# Sheet1.net
KiCad netlist of a schematic drawn in Altium Designer
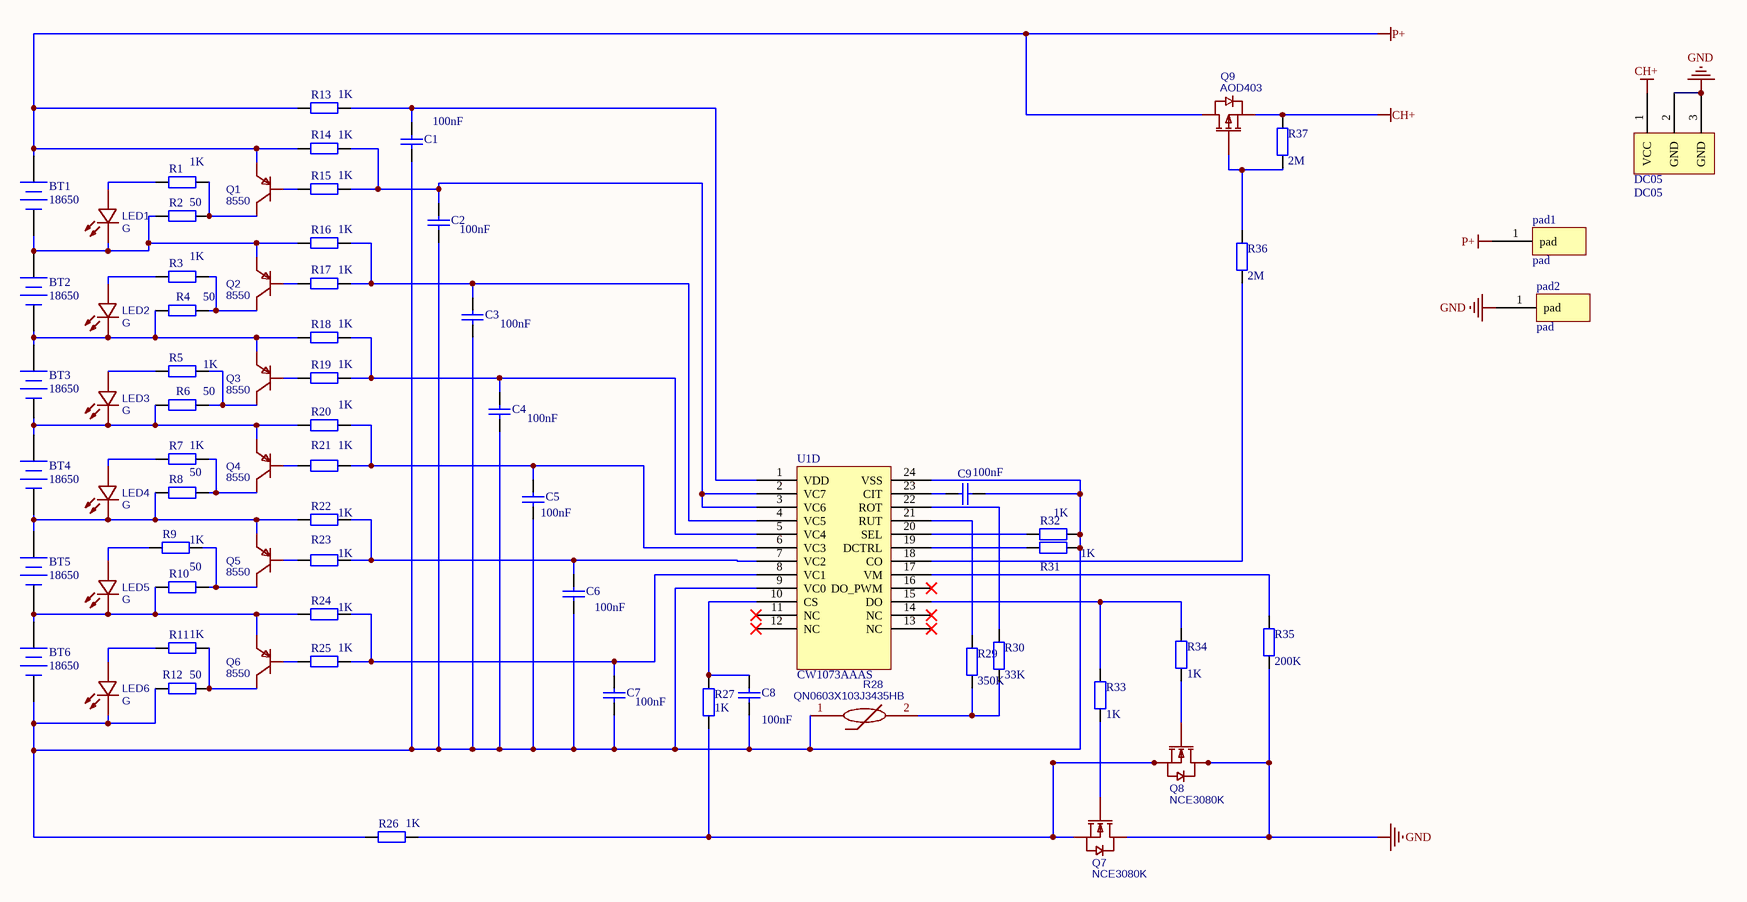
[diagram p0: Sheet1.SchDoc]

(export (version "E")
  (design (tool "Eeschema 10.0.6"))
  (components
    (comp (ref "BT1")
      (value "18650")
      (footprint "18650-贴片")
      (description "Multicell Battery")
      (fields (field (name "PUBLISHER") "Altium Limited"))
      (libsource (lib "Miscellaneous Devices") (part "Battery"))
    )
    (comp (ref "BT2")
      (value "18650")
      (footprint "18650-贴片")
      (description "Multicell Battery")
      (fields (field (name "PUBLISHER") "Altium Limited"))
      (libsource (lib "Miscellaneous Devices") (part "Battery"))
    )
    (comp (ref "BT3")
      (value "18650")
      (footprint "18650-贴片")
      (description "Multicell Battery")
      (fields (field (name "PUBLISHER") "Altium Limited"))
      (libsource (lib "Miscellaneous Devices") (part "Battery"))
    )
    (comp (ref "BT4")
      (value "18650")
      (footprint "18650-贴片")
      (description "Multicell Battery")
      (fields (field (name "PUBLISHER") "Altium Limited"))
      (libsource (lib "Miscellaneous Devices") (part "Battery"))
    )
    (comp (ref "BT5")
      (value "18650")
      (footprint "18650-贴片")
      (description "Multicell Battery")
      (fields (field (name "PUBLISHER") "Altium Limited"))
      (libsource (lib "Miscellaneous Devices") (part "Battery"))
    )
    (comp (ref "BT6")
      (value "18650")
      (footprint "18650-贴片")
      (description "Multicell Battery")
      (fields (field (name "PUBLISHER") "Altium Limited"))
      (libsource (lib "Miscellaneous Devices") (part "Battery"))
    )
    (comp (ref "C1")
      (value "100nF")
      (footprint "0805_C")
      (description "Capacitor")
      (fields (field (name "PUBLISHER") "Altium Limited"))
      (libsource (lib "Miscellaneous Devices") (part "Cap"))
    )
    (comp (ref "C2")
      (value "100nF")
      (footprint "0805_C")
      (description "Capacitor")
      (fields (field (name "PUBLISHER") "Altium Limited"))
      (libsource (lib "Miscellaneous Devices") (part "Cap"))
    )
    (comp (ref "C3")
      (value "100nF")
      (footprint "0805_C")
      (description "Capacitor")
      (fields (field (name "PUBLISHER") "Altium Limited"))
      (libsource (lib "Miscellaneous Devices") (part "Cap"))
    )
    (comp (ref "C4")
      (value "100nF")
      (footprint "0805_C")
      (description "Capacitor")
      (fields (field (name "PUBLISHER") "Altium Limited"))
      (libsource (lib "Miscellaneous Devices") (part "Cap"))
    )
    (comp (ref "C5")
      (value "100nF")
      (footprint "0805_C")
      (description "Capacitor")
      (fields (field (name "PUBLISHER") "Altium Limited"))
      (libsource (lib "Miscellaneous Devices") (part "Cap"))
    )
    (comp (ref "C6")
      (value "100nF")
      (footprint "0805_C")
      (description "Capacitor")
      (fields (field (name "PUBLISHER") "Altium Limited"))
      (libsource (lib "Miscellaneous Devices") (part "Cap"))
    )
    (comp (ref "C7")
      (value "100nF")
      (footprint "0805_C")
      (description "Capacitor")
      (fields (field (name "PUBLISHER") "Altium Limited"))
      (libsource (lib "Miscellaneous Devices") (part "Cap"))
    )
    (comp (ref "C8")
      (value "100nF")
      (footprint "0805_C")
      (description "Capacitor")
      (fields (field (name "PUBLISHER") "Altium Limited"))
      (libsource (lib "Miscellaneous Devices") (part "Cap"))
    )
    (comp (ref "C9")
      (value "100nF")
      (footprint "0805_C")
      (description "Capacitor")
      (fields (field (name "PUBLISHER") "Altium Limited"))
      (libsource (lib "Miscellaneous Devices") (part "Cap"))
    )
    (comp (ref "DC05")
      (value "DC05")
      (footprint "DC-005 - duplicate")
      (description "DC05电源")
      (libsource (lib "elin私人订制") (part "DC05"))
    )
    (comp (ref "LED1")
      (value "G")
      (footprint "LED_0805")
      (fields
        (field (name "BOM_SUPPLIER PART") "C264445")
        (field (name "BOM_MANUFACTURER PART") "19-21CUTD/S3484/TR8")
        (field (name "CONTRIBUTOR") "LCSC")
      )
      (libsource (lib "altium-import") (part "root_1_G_"))
    )
    (comp (ref "LED2")
      (value "G")
      (footprint "LED_0805")
      (fields
        (field (name "BOM_SUPPLIER PART") "C264445")
        (field (name "BOM_MANUFACTURER PART") "19-21CUTD/S3484/TR8")
        (field (name "CONTRIBUTOR") "LCSC")
      )
      (libsource (lib "altium-import") (part "root_1_G_"))
    )
    (comp (ref "LED3")
      (value "G")
      (footprint "LED_0805")
      (fields
        (field (name "BOM_SUPPLIER PART") "C264445")
        (field (name "BOM_MANUFACTURER PART") "19-21CUTD/S3484/TR8")
        (field (name "CONTRIBUTOR") "LCSC")
      )
      (libsource (lib "altium-import") (part "root_1_G_"))
    )
    (comp (ref "LED4")
      (value "G")
      (footprint "LED_0805")
      (fields
        (field (name "BOM_SUPPLIER PART") "C264445")
        (field (name "BOM_MANUFACTURER PART") "19-21CUTD/S3484/TR8")
        (field (name "CONTRIBUTOR") "LCSC")
      )
      (libsource (lib "altium-import") (part "root_1_G_"))
    )
    (comp (ref "LED5")
      (value "G")
      (footprint "LED_0805")
      (fields
        (field (name "BOM_SUPPLIER PART") "C264445")
        (field (name "BOM_MANUFACTURER PART") "19-21CUTD/S3484/TR8")
        (field (name "CONTRIBUTOR") "LCSC")
      )
      (libsource (lib "altium-import") (part "root_1_G_"))
    )
    (comp (ref "LED6")
      (value "G")
      (footprint "LED_0805")
      (fields
        (field (name "BOM_SUPPLIER PART") "C264445")
        (field (name "BOM_MANUFACTURER PART") "19-21CUTD/S3484/TR8")
        (field (name "CONTRIBUTOR") "LCSC")
      )
      (libsource (lib "altium-import") (part "root_1_G_"))
    )
    (comp (ref "pad1") (value "pad") (footprint "PAD3*3") (libsource (lib "elin私人订制") (part "pad1")))
    (comp (ref "pad2") (value "pad") (footprint "PAD3*3") (libsource (lib "elin私人订制") (part "pad1")))
    (comp (ref "Q1")
      (value "8550")
      (footprint "SOT23")
      (fields
        (field (name "BOM_SUPPLIER PART") "C305484")
        (field (name "BOM_MANUFACTURER PART") "S8550M-D")
        (field (name "CONTRIBUTOR") "LCSC")
      )
      (libsource (lib "altium-import") (part "root_2_8550_"))
    )
    (comp (ref "Q2")
      (value "8550")
      (footprint "SOT23")
      (fields
        (field (name "BOM_SUPPLIER PART") "C305484")
        (field (name "BOM_MANUFACTURER PART") "S8550M-D")
        (field (name "CONTRIBUTOR") "LCSC")
      )
      (libsource (lib "altium-import") (part "root_2_8550_"))
    )
    (comp (ref "Q3")
      (value "8550")
      (footprint "SOT23")
      (fields
        (field (name "BOM_SUPPLIER PART") "C305484")
        (field (name "BOM_MANUFACTURER PART") "S8550M-D")
        (field (name "CONTRIBUTOR") "LCSC")
      )
      (libsource (lib "altium-import") (part "root_2_8550_"))
    )
    (comp (ref "Q4")
      (value "8550")
      (footprint "SOT23")
      (fields
        (field (name "BOM_SUPPLIER PART") "C305484")
        (field (name "BOM_MANUFACTURER PART") "S8550M-D")
        (field (name "CONTRIBUTOR") "LCSC")
      )
      (libsource (lib "altium-import") (part "root_2_8550_"))
    )
    (comp (ref "Q5")
      (value "8550")
      (footprint "SOT23")
      (fields
        (field (name "BOM_SUPPLIER PART") "C305484")
        (field (name "BOM_MANUFACTURER PART") "S8550M-D")
        (field (name "CONTRIBUTOR") "LCSC")
      )
      (libsource (lib "altium-import") (part "root_2_8550_"))
    )
    (comp (ref "Q6")
      (value "8550")
      (footprint "SOT23")
      (fields
        (field (name "BOM_SUPPLIER PART") "C305484")
        (field (name "BOM_MANUFACTURER PART") "S8550M-D")
        (field (name "CONTRIBUTOR") "LCSC")
      )
      (libsource (lib "altium-import") (part "root_2_8550_"))
    )
    (comp (ref "Q7")
      (value "NCE3080K")
      (footprint "LC-TO-252-2")
      (fields (field (name "BOM_SUPPLIER PART") "C108901"))
      (libsource (lib "altium-import") (part "root_3_NCE3080K_"))
    )
    (comp (ref "Q8")
      (value "NCE3080K")
      (footprint "LC-TO-252-2")
      (fields (field (name "BOM_SUPPLIER PART") "C108901"))
      (libsource (lib "altium-import") (part "root_3_NCE3080K_"))
    )
    (comp (ref "Q9")
      (value "AOD403")
      (footprint "LC-TO-252-2")
      (fields (field (name "BOM_SUPPLIER PART") "C28969"))
      (libsource (lib "altium-import") (part "root_1_AOD403_"))
    )
    (comp (ref "R1")
      (value "1K")
      (footprint "0603-R")
      (description "Resistor")
      (fields (field (name "PUBLISHER") "Altium Limited"))
      (libsource (lib "Miscellaneous Devices") (part "Res2"))
    )
    (comp (ref "R2")
      (value "50")
      (footprint "LC-2512_R")
      (description "Resistor")
      (fields (field (name "PUBLISHER") "Altium Limited"))
      (libsource (lib "Miscellaneous Devices") (part "Res2"))
    )
    (comp (ref "R3")
      (value "1K")
      (footprint "0603-R")
      (description "Resistor")
      (fields (field (name "PUBLISHER") "Altium Limited"))
      (libsource (lib "Miscellaneous Devices") (part "Res2"))
    )
    (comp (ref "R4")
      (value "50")
      (footprint "LC-2512_R")
      (description "Resistor")
      (fields (field (name "PUBLISHER") "Altium Limited"))
      (libsource (lib "Miscellaneous Devices") (part "Res2"))
    )
    (comp (ref "R5")
      (value "1K")
      (footprint "0603-R")
      (description "Resistor")
      (fields (field (name "PUBLISHER") "Altium Limited"))
      (libsource (lib "Miscellaneous Devices") (part "Res2"))
    )
    (comp (ref "R6")
      (value "50")
      (footprint "LC-2512_R")
      (description "Resistor")
      (fields (field (name "PUBLISHER") "Altium Limited"))
      (libsource (lib "Miscellaneous Devices") (part "Res2"))
    )
    (comp (ref "R7")
      (value "1K")
      (footprint "0603-R")
      (description "Resistor")
      (fields (field (name "PUBLISHER") "Altium Limited"))
      (libsource (lib "Miscellaneous Devices") (part "Res2"))
    )
    (comp (ref "R8")
      (value "50")
      (footprint "LC-2512_R")
      (description "Resistor")
      (fields (field (name "PUBLISHER") "Altium Limited"))
      (libsource (lib "Miscellaneous Devices") (part "Res2"))
    )
    (comp (ref "R9")
      (value "1K")
      (footprint "0603-R")
      (description "Resistor")
      (fields (field (name "PUBLISHER") "Altium Limited"))
      (libsource (lib "Miscellaneous Devices") (part "Res2"))
    )
    (comp (ref "R10")
      (value "50")
      (footprint "LC-2512_R")
      (description "Resistor")
      (fields (field (name "PUBLISHER") "Altium Limited"))
      (libsource (lib "Miscellaneous Devices") (part "Res2"))
    )
    (comp (ref "R11")
      (value "1K")
      (footprint "0603-R")
      (description "Resistor")
      (fields (field (name "PUBLISHER") "Altium Limited"))
      (libsource (lib "Miscellaneous Devices") (part "Res2"))
    )
    (comp (ref "R12")
      (value "50")
      (footprint "LC-2512_R")
      (description "Resistor")
      (fields (field (name "PUBLISHER") "Altium Limited"))
      (libsource (lib "Miscellaneous Devices") (part "Res2"))
    )
    (comp (ref "R13")
      (value "1K")
      (footprint "0603-R")
      (description "Resistor")
      (fields (field (name "PUBLISHER") "Altium Limited"))
      (libsource (lib "Miscellaneous Devices") (part "Res2"))
    )
    (comp (ref "R14")
      (value "1K")
      (footprint "0603-R")
      (description "Resistor")
      (fields (field (name "PUBLISHER") "Altium Limited"))
      (libsource (lib "Miscellaneous Devices") (part "Res2"))
    )
    (comp (ref "R15")
      (value "1K")
      (footprint "0603-R")
      (description "Resistor")
      (fields (field (name "PUBLISHER") "Altium Limited"))
      (libsource (lib "Miscellaneous Devices") (part "Res2"))
    )
    (comp (ref "R16")
      (value "1K")
      (footprint "0603-R")
      (description "Resistor")
      (fields (field (name "PUBLISHER") "Altium Limited"))
      (libsource (lib "Miscellaneous Devices") (part "Res2"))
    )
    (comp (ref "R17")
      (value "1K")
      (footprint "0603-R")
      (description "Resistor")
      (fields (field (name "PUBLISHER") "Altium Limited"))
      (libsource (lib "Miscellaneous Devices") (part "Res2"))
    )
    (comp (ref "R18")
      (value "1K")
      (footprint "0603-R")
      (description "Resistor")
      (fields (field (name "PUBLISHER") "Altium Limited"))
      (libsource (lib "Miscellaneous Devices") (part "Res2"))
    )
    (comp (ref "R19")
      (value "1K")
      (footprint "0603-R")
      (description "Resistor")
      (fields (field (name "PUBLISHER") "Altium Limited"))
      (libsource (lib "Miscellaneous Devices") (part "Res2"))
    )
    (comp (ref "R20")
      (value "1K")
      (footprint "0603-R")
      (description "Resistor")
      (fields (field (name "PUBLISHER") "Altium Limited"))
      (libsource (lib "Miscellaneous Devices") (part "Res2"))
    )
    (comp (ref "R21")
      (value "1K")
      (footprint "0603-R")
      (description "Resistor")
      (fields (field (name "PUBLISHER") "Altium Limited"))
      (libsource (lib "Miscellaneous Devices") (part "Res2"))
    )
    (comp (ref "R22")
      (value "1K")
      (footprint "0603-R")
      (description "Resistor")
      (fields (field (name "PUBLISHER") "Altium Limited"))
      (libsource (lib "Miscellaneous Devices") (part "Res2"))
    )
    (comp (ref "R23")
      (value "1K")
      (footprint "0603-R")
      (description "Resistor")
      (fields (field (name "PUBLISHER") "Altium Limited"))
      (libsource (lib "Miscellaneous Devices") (part "Res2"))
    )
    (comp (ref "R24")
      (value "1K")
      (footprint "0603-R")
      (description "Resistor")
      (fields (field (name "PUBLISHER") "Altium Limited"))
      (libsource (lib "Miscellaneous Devices") (part "Res2"))
    )
    (comp (ref "R25")
      (value "1K")
      (footprint "0603-R")
      (description "Resistor")
      (fields (field (name "PUBLISHER") "Altium Limited"))
      (libsource (lib "Miscellaneous Devices") (part "Res2"))
    )
    (comp (ref "R26")
      (value "1K")
      (footprint "0603-R")
      (description "Resistor")
      (fields (field (name "PUBLISHER") "Altium Limited"))
      (libsource (lib "Miscellaneous Devices") (part "Res2"))
    )
    (comp (ref "R27")
      (value "1K")
      (footprint "0603-R")
      (description "Resistor")
      (fields (field (name "PUBLISHER") "Altium Limited"))
      (libsource (lib "") (part "Res2_1"))
    )
    (comp (ref "R28")
      (value "QN0603X103J3435HB")
      (footprint "0603-R")
      (fields (field (name "BOM_SUPPLIER PART") "C700828") (field (name "CONTRIBUTOR") "LCSC"))
      (libsource (lib "altium-import") (part "root_0_QN0603X103J3435HB_"))
    )
    (comp (ref "R29")
      (value "350K")
      (footprint "0603-R")
      (description "Resistor")
      (fields (field (name "PUBLISHER") "Altium Limited"))
      (libsource (lib "") (part "Res2_1"))
    )
    (comp (ref "R30")
      (value "33K")
      (footprint "0603-R")
      (description "Resistor")
      (fields (field (name "PUBLISHER") "Altium Limited"))
      (libsource (lib "") (part "Res2_1"))
    )
    (comp (ref "R31")
      (value "1K")
      (footprint "0603-R")
      (description "Resistor")
      (fields (field (name "PUBLISHER") "Altium Limited"))
      (libsource (lib "Miscellaneous Devices") (part "Res2"))
    )
    (comp (ref "R32")
      (value "1K")
      (footprint "0603-R")
      (description "Resistor")
      (fields (field (name "PUBLISHER") "Altium Limited"))
      (libsource (lib "Miscellaneous Devices") (part "Res2"))
    )
    (comp (ref "R33")
      (value "1K")
      (footprint "0603-R")
      (description "Resistor")
      (fields (field (name "PUBLISHER") "Altium Limited"))
      (libsource (lib "") (part "Res2_1"))
    )
    (comp (ref "R34")
      (value "1K")
      (footprint "0603-R")
      (description "Resistor")
      (fields (field (name "PUBLISHER") "Altium Limited"))
      (libsource (lib "") (part "Res2_1"))
    )
    (comp (ref "R35")
      (value "200K")
      (footprint "0603-R")
      (description "Resistor")
      (fields (field (name "PUBLISHER") "Altium Limited"))
      (libsource (lib "") (part "Res2_1"))
    )
    (comp (ref "R36")
      (value "2M")
      (footprint "0603-R")
      (description "Resistor")
      (fields (field (name "PUBLISHER") "Altium Limited"))
      (libsource (lib "") (part "Res2_1"))
    )
    (comp (ref "R37")
      (value "2M")
      (footprint "0603-R")
      (description "Resistor")
      (fields (field (name "PUBLISHER") "Altium Limited"))
      (libsource (lib "") (part "Res2_1"))
    )
    (comp (ref "U1")
      (value "CW1073AAAS")
      (footprint "LC-SSOP-24_208mil")
      (libsource (lib "Schlib1") (part "Component_1"))
    )
  )
  (nets
    (net (code "1") (name "CH+") (class "Default")
      (node (ref "DC05") (pin "1") (pinfunction "VCC_1") (pintype "passive"))
      (node (ref "Q9") (pin "3") (pinfunction "S_3") (pintype "passive"))
      (node (ref "R37") (pin "2") (pinfunction "2_2") (pintype "passive"))
    )
    (net (code "2") (name "GND") (class "Default")
      (node (ref "DC05") (pin "2") (pinfunction "GND_2") (pintype "passive"))
      (node (ref "DC05") (pin "3") (pinfunction "GND_3") (pintype "passive"))
      (node (ref "Q7") (pin "2") (pinfunction "D_2") (pintype "passive"))
      (node (ref "Q8") (pin "2") (pinfunction "D_2") (pintype "passive"))
      (node (ref "R35") (pin "1") (pinfunction "1_1") (pintype "passive"))
      (node (ref "pad2") (pin "1") (pinfunction "pad_1") (pintype "passive"))
    )
    (net (code "3") (name "Net-(BT1--)") (class "Default")
      (node (ref "BT1") (pin "2") (pinfunction "-_2") (pintype "passive"))
      (node (ref "BT2") (pin "1") (pinfunction "+_1") (pintype "passive"))
      (node (ref "LED1") (pin "2") (pinfunction "K_2") (pintype "passive"))
      (node (ref "Q2") (pin "2") (pinfunction "E_2") (pintype "passive"))
      (node (ref "R16") (pin "1") (pinfunction "1_1") (pintype "passive"))
      (node (ref "R2") (pin "1") (pinfunction "1_1") (pintype "passive"))
    )
    (net (code "4") (name "Net-(BT2--)") (class "Default")
      (node (ref "BT2") (pin "2") (pinfunction "-_2") (pintype "passive"))
      (node (ref "BT3") (pin "1") (pinfunction "+_1") (pintype "passive"))
      (node (ref "LED2") (pin "2") (pinfunction "K_2") (pintype "passive"))
      (node (ref "Q3") (pin "2") (pinfunction "E_2") (pintype "passive"))
      (node (ref "R18") (pin "1") (pinfunction "1_1") (pintype "passive"))
      (node (ref "R4") (pin "1") (pinfunction "1_1") (pintype "passive"))
    )
    (net (code "5") (name "Net-(BT3--)") (class "Default")
      (node (ref "BT3") (pin "2") (pinfunction "-_2") (pintype "passive"))
      (node (ref "BT4") (pin "1") (pinfunction "+_1") (pintype "passive"))
      (node (ref "LED3") (pin "2") (pinfunction "K_2") (pintype "passive"))
      (node (ref "Q4") (pin "2") (pinfunction "E_2") (pintype "passive"))
      (node (ref "R20") (pin "1") (pinfunction "1_1") (pintype "passive"))
      (node (ref "R6") (pin "1") (pinfunction "1_1") (pintype "passive"))
    )
    (net (code "6") (name "Net-(BT4--)") (class "Default")
      (node (ref "BT4") (pin "2") (pinfunction "-_2") (pintype "passive"))
      (node (ref "BT5") (pin "1") (pinfunction "+_1") (pintype "passive"))
      (node (ref "LED4") (pin "2") (pinfunction "K_2") (pintype "passive"))
      (node (ref "Q5") (pin "2") (pinfunction "E_2") (pintype "passive"))
      (node (ref "R22") (pin "1") (pinfunction "1_1") (pintype "passive"))
      (node (ref "R8") (pin "1") (pinfunction "1_1") (pintype "passive"))
    )
    (net (code "7") (name "Net-(BT5--)") (class "Default")
      (node (ref "BT5") (pin "2") (pinfunction "-_2") (pintype "passive"))
      (node (ref "BT6") (pin "1") (pinfunction "+_1") (pintype "passive"))
      (node (ref "LED5") (pin "2") (pinfunction "K_2") (pintype "passive"))
      (node (ref "Q6") (pin "2") (pinfunction "E_2") (pintype "passive"))
      (node (ref "R10") (pin "1") (pinfunction "1_1") (pintype "passive"))
      (node (ref "R24") (pin "1") (pinfunction "1_1") (pintype "passive"))
    )
    (net (code "8") (name "Net-(BT6--)") (class "Default")
      (node (ref "BT6") (pin "2") (pinfunction "-_2") (pintype "passive"))
      (node (ref "C1") (pin "2") (pinfunction "2_2") (pintype "passive"))
      (node (ref "C2") (pin "2") (pinfunction "2_2") (pintype "passive"))
      (node (ref "C3") (pin "2") (pinfunction "2_2") (pintype "passive"))
      (node (ref "C4") (pin "2") (pinfunction "2_2") (pintype "passive"))
      (node (ref "C5") (pin "2") (pinfunction "2_2") (pintype "passive"))
      (node (ref "C6") (pin "2") (pinfunction "2_2") (pintype "passive"))
      (node (ref "C7") (pin "2") (pinfunction "2_2") (pintype "passive"))
      (node (ref "C8") (pin "2") (pinfunction "2_2") (pintype "passive"))
      (node (ref "C9") (pin "1") (pinfunction "1_1") (pintype "passive"))
      (node (ref "LED6") (pin "2") (pinfunction "K_2") (pintype "passive"))
      (node (ref "R12") (pin "1") (pinfunction "1_1") (pintype "passive"))
      (node (ref "R26") (pin "1") (pinfunction "1_1") (pintype "passive"))
      (node (ref "R28") (pin "1") (pinfunction "1_1") (pintype "passive"))
      (node (ref "R31") (pin "2") (pinfunction "2_2") (pintype "passive"))
      (node (ref "R32") (pin "2") (pinfunction "2_2") (pintype "passive"))
      (node (ref "U1") (pin "24") (pinfunction "VSS_24") (pintype "passive"))
      (node (ref "U1") (pin "9") (pinfunction "VC0_9") (pintype "passive"))
    )
    (net (code "9") (name "Net-(LED1-A)") (class "Default")
      (node (ref "LED1") (pin "1") (pinfunction "A_1") (pintype "passive"))
      (node (ref "R1") (pin "1") (pinfunction "1_1") (pintype "passive"))
    )
    (net (code "10") (name "Net-(LED2-A)") (class "Default")
      (node (ref "LED2") (pin "1") (pinfunction "A_1") (pintype "passive"))
      (node (ref "R3") (pin "1") (pinfunction "1_1") (pintype "passive"))
    )
    (net (code "11") (name "Net-(LED3-A)") (class "Default")
      (node (ref "LED3") (pin "1") (pinfunction "A_1") (pintype "passive"))
      (node (ref "R5") (pin "1") (pinfunction "1_1") (pintype "passive"))
    )
    (net (code "12") (name "Net-(LED4-A)") (class "Default")
      (node (ref "LED4") (pin "1") (pinfunction "A_1") (pintype "passive"))
      (node (ref "R7") (pin "1") (pinfunction "1_1") (pintype "passive"))
    )
    (net (code "13") (name "Net-(LED5-A)") (class "Default")
      (node (ref "LED5") (pin "1") (pinfunction "A_1") (pintype "passive"))
      (node (ref "R9") (pin "1") (pinfunction "1_1") (pintype "passive"))
    )
    (net (code "14") (name "Net-(LED6-A)") (class "Default")
      (node (ref "LED6") (pin "1") (pinfunction "A_1") (pintype "passive"))
      (node (ref "R11") (pin "1") (pinfunction "1_1") (pintype "passive"))
    )
    (net (code "15") (name "Net-(Q1-B)") (class "Default")
      (node (ref "Q1") (pin "1") (pinfunction "B_1") (pintype "passive"))
      (node (ref "R15") (pin "1") (pinfunction "1_1") (pintype "passive"))
    )
    (net (code "16") (name "Net-(Q1-C)") (class "Default")
      (node (ref "Q1") (pin "3") (pinfunction "C_3") (pintype "passive"))
      (node (ref "R1") (pin "2") (pinfunction "2_2") (pintype "passive"))
      (node (ref "R2") (pin "2") (pinfunction "2_2") (pintype "passive"))
    )
    (net (code "17") (name "Net-(Q2-B)") (class "Default")
      (node (ref "Q2") (pin "1") (pinfunction "B_1") (pintype "passive"))
      (node (ref "R17") (pin "1") (pinfunction "1_1") (pintype "passive"))
    )
    (net (code "18") (name "Net-(Q2-C)") (class "Default")
      (node (ref "Q2") (pin "3") (pinfunction "C_3") (pintype "passive"))
      (node (ref "R3") (pin "2") (pinfunction "2_2") (pintype "passive"))
      (node (ref "R4") (pin "2") (pinfunction "2_2") (pintype "passive"))
    )
    (net (code "19") (name "Net-(Q3-B)") (class "Default")
      (node (ref "Q3") (pin "1") (pinfunction "B_1") (pintype "passive"))
      (node (ref "R19") (pin "1") (pinfunction "1_1") (pintype "passive"))
    )
    (net (code "20") (name "Net-(Q3-C)") (class "Default")
      (node (ref "Q3") (pin "3") (pinfunction "C_3") (pintype "passive"))
      (node (ref "R5") (pin "2") (pinfunction "2_2") (pintype "passive"))
      (node (ref "R6") (pin "2") (pinfunction "2_2") (pintype "passive"))
    )
    (net (code "21") (name "Net-(Q4-B)") (class "Default")
      (node (ref "Q4") (pin "1") (pinfunction "B_1") (pintype "passive"))
      (node (ref "R21") (pin "1") (pinfunction "1_1") (pintype "passive"))
    )
    (net (code "22") (name "Net-(Q4-C)") (class "Default")
      (node (ref "Q4") (pin "3") (pinfunction "C_3") (pintype "passive"))
      (node (ref "R7") (pin "2") (pinfunction "2_2") (pintype "passive"))
      (node (ref "R8") (pin "2") (pinfunction "2_2") (pintype "passive"))
    )
    (net (code "23") (name "Net-(Q5-B)") (class "Default")
      (node (ref "Q5") (pin "1") (pinfunction "B_1") (pintype "passive"))
      (node (ref "R23") (pin "1") (pinfunction "1_1") (pintype "passive"))
    )
    (net (code "24") (name "Net-(Q5-C)") (class "Default")
      (node (ref "Q5") (pin "3") (pinfunction "C_3") (pintype "passive"))
      (node (ref "R10") (pin "2") (pinfunction "2_2") (pintype "passive"))
      (node (ref "R9") (pin "2") (pinfunction "2_2") (pintype "passive"))
    )
    (net (code "25") (name "Net-(Q6-B)") (class "Default")
      (node (ref "Q6") (pin "1") (pinfunction "B_1") (pintype "passive"))
      (node (ref "R25") (pin "1") (pinfunction "1_1") (pintype "passive"))
    )
    (net (code "26") (name "Net-(Q6-C)") (class "Default")
      (node (ref "Q6") (pin "3") (pinfunction "C_3") (pintype "passive"))
      (node (ref "R11") (pin "2") (pinfunction "2_2") (pintype "passive"))
      (node (ref "R12") (pin "2") (pinfunction "2_2") (pintype "passive"))
    )
    (net (code "27") (name "Net-(Q7-G)") (class "Default")
      (node (ref "Q7") (pin "1") (pinfunction "G_1") (pintype "passive"))
      (node (ref "R33") (pin "1") (pinfunction "1_1") (pintype "passive"))
    )
    (net (code "28") (name "Net-(Q7-S)") (class "Default")
      (node (ref "Q7") (pin "3") (pinfunction "S_3") (pintype "passive"))
      (node (ref "Q8") (pin "3") (pinfunction "S_3") (pintype "passive"))
      (node (ref "R26") (pin "2") (pinfunction "2_2") (pintype "passive"))
      (node (ref "R27") (pin "1") (pinfunction "1_1") (pintype "passive"))
    )
    (net (code "29") (name "Net-(Q8-G)") (class "Default")
      (node (ref "Q8") (pin "1") (pinfunction "G_1") (pintype "passive"))
      (node (ref "R34") (pin "1") (pinfunction "1_1") (pintype "passive"))
    )
    (net (code "30") (name "Net-(Q9-G)") (class "Default")
      (node (ref "Q9") (pin "1") (pinfunction "G_1") (pintype "passive"))
      (node (ref "R36") (pin "2") (pinfunction "2_2") (pintype "passive"))
      (node (ref "R37") (pin "1") (pinfunction "1_1") (pintype "passive"))
    )
    (net (code "31") (name "Net-(R28-Pad2)") (class "Default")
      (node (ref "R28") (pin "2") (pinfunction "2_2") (pintype "passive"))
      (node (ref "R29") (pin "1") (pinfunction "1_1") (pintype "passive"))
      (node (ref "R30") (pin "1") (pinfunction "1_1") (pintype "passive"))
    )
    (net (code "32") (name "Net-(U1D-CIT)") (class "Default")
      (node (ref "C9") (pin "2") (pinfunction "2_2") (pintype "passive"))
      (node (ref "U1") (pin "23") (pinfunction "CIT_23") (pintype "passive"))
    )
    (net (code "33") (name "Net-(U1D-CO)") (class "Default")
      (node (ref "R36") (pin "1") (pinfunction "1_1") (pintype "passive"))
      (node (ref "U1") (pin "18") (pinfunction "CO_18") (pintype "passive"))
    )
    (net (code "34") (name "Net-(U1D-CS)") (class "Default")
      (node (ref "C8") (pin "1") (pinfunction "1_1") (pintype "passive"))
      (node (ref "R27") (pin "2") (pinfunction "2_2") (pintype "passive"))
      (node (ref "U1") (pin "10") (pinfunction "CS_10") (pintype "passive"))
    )
    (net (code "35") (name "Net-(U1D-DCTRL)") (class "Default")
      (node (ref "R31") (pin "1") (pinfunction "1_1") (pintype "passive"))
      (node (ref "U1") (pin "19") (pinfunction "DCTRL_19") (pintype "passive"))
    )
    (net (code "36") (name "Net-(U1D-DO)") (class "Default")
      (node (ref "R33") (pin "2") (pinfunction "2_2") (pintype "passive"))
      (node (ref "R34") (pin "2") (pinfunction "2_2") (pintype "passive"))
      (node (ref "U1") (pin "15") (pinfunction "DO_15") (pintype "passive"))
    )
    (net (code "37") (name "Net-(U1D-ROT)") (class "Default")
      (node (ref "R30") (pin "2") (pinfunction "2_2") (pintype "passive"))
      (node (ref "U1") (pin "22") (pinfunction "ROT_22") (pintype "passive"))
    )
    (net (code "38") (name "Net-(U1D-RUT)") (class "Default")
      (node (ref "R29") (pin "2") (pinfunction "2_2") (pintype "passive"))
      (node (ref "U1") (pin "21") (pinfunction "RUT_21") (pintype "passive"))
    )
    (net (code "39") (name "Net-(U1D-SEL)") (class "Default")
      (node (ref "R32") (pin "1") (pinfunction "1_1") (pintype "passive"))
      (node (ref "U1") (pin "20") (pinfunction "SEL_20") (pintype "passive"))
    )
    (net (code "40") (name "Net-(U1D-VC1)") (class "Default")
      (node (ref "C7") (pin "1") (pinfunction "1_1") (pintype "passive"))
      (node (ref "R24") (pin "2") (pinfunction "2_2") (pintype "passive"))
      (node (ref "R25") (pin "2") (pinfunction "2_2") (pintype "passive"))
      (node (ref "U1") (pin "8") (pinfunction "VC1_8") (pintype "passive"))
    )
    (net (code "41") (name "Net-(U1D-VC2)") (class "Default")
      (node (ref "C6") (pin "1") (pinfunction "1_1") (pintype "passive"))
      (node (ref "R22") (pin "2") (pinfunction "2_2") (pintype "passive"))
      (node (ref "R23") (pin "2") (pinfunction "2_2") (pintype "passive"))
      (node (ref "U1") (pin "7") (pinfunction "VC2_7") (pintype "passive"))
    )
    (net (code "42") (name "Net-(U1D-VC3)") (class "Default")
      (node (ref "C5") (pin "1") (pinfunction "1_1") (pintype "passive"))
      (node (ref "R20") (pin "2") (pinfunction "2_2") (pintype "passive"))
      (node (ref "R21") (pin "2") (pinfunction "2_2") (pintype "passive"))
      (node (ref "U1") (pin "6") (pinfunction "VC3_6") (pintype "passive"))
    )
    (net (code "43") (name "Net-(U1D-VC4)") (class "Default")
      (node (ref "C4") (pin "1") (pinfunction "1_1") (pintype "passive"))
      (node (ref "R18") (pin "2") (pinfunction "2_2") (pintype "passive"))
      (node (ref "R19") (pin "2") (pinfunction "2_2") (pintype "passive"))
      (node (ref "U1") (pin "5") (pinfunction "VC4_5") (pintype "passive"))
    )
    (net (code "44") (name "Net-(U1D-VC5)") (class "Default")
      (node (ref "C3") (pin "1") (pinfunction "1_1") (pintype "passive"))
      (node (ref "R16") (pin "2") (pinfunction "2_2") (pintype "passive"))
      (node (ref "R17") (pin "2") (pinfunction "2_2") (pintype "passive"))
      (node (ref "U1") (pin "4") (pinfunction "VC5_4") (pintype "passive"))
    )
    (net (code "45") (name "Net-(U1D-VC6)") (class "Default")
      (node (ref "C2") (pin "1") (pinfunction "1_1") (pintype "passive"))
      (node (ref "R14") (pin "2") (pinfunction "2_2") (pintype "passive"))
      (node (ref "R15") (pin "2") (pinfunction "2_2") (pintype "passive"))
      (node (ref "U1") (pin "2") (pinfunction "VC7_2") (pintype "passive"))
      (node (ref "U1") (pin "3") (pinfunction "VC6_3") (pintype "passive"))
    )
    (net (code "46") (name "Net-(U1D-VDD)") (class "Default")
      (node (ref "C1") (pin "1") (pinfunction "1_1") (pintype "passive"))
      (node (ref "R13") (pin "2") (pinfunction "2_2") (pintype "passive"))
      (node (ref "U1") (pin "1") (pinfunction "VDD_1") (pintype "passive"))
    )
    (net (code "47") (name "Net-(U1D-VM)") (class "Default")
      (node (ref "R35") (pin "2") (pinfunction "2_2") (pintype "passive"))
      (node (ref "U1") (pin "17") (pinfunction "VM_17") (pintype "passive"))
    )
    (net (code "48") (name "P+") (class "Default")
      (node (ref "BT1") (pin "1") (pinfunction "+_1") (pintype "passive"))
      (node (ref "Q1") (pin "2") (pinfunction "E_2") (pintype "passive"))
      (node (ref "Q9") (pin "2") (pinfunction "D_2") (pintype "passive"))
      (node (ref "R13") (pin "1") (pinfunction "1_1") (pintype "passive"))
      (node (ref "R14") (pin "1") (pinfunction "1_1") (pintype "passive"))
      (node (ref "pad1") (pin "1") (pinfunction "pad_1") (pintype "passive"))
    )
    (net (code "49") (name "unconnected-(U1D-DO_PWM-Pad16)") (class "Default")
      (node (ref "U1") (pin "16") (pinfunction "DO_PWM_16") (pintype "passive+no_connect"))
    )
    (net (code "50") (name "unconnected-(U1D-NC-Pad11)") (class "Default")
      (node (ref "U1") (pin "11") (pinfunction "NC_11") (pintype "passive+no_connect"))
    )
    (net (code "51") (name "unconnected-(U1D-NC-Pad12)") (class "Default")
      (node (ref "U1") (pin "12") (pinfunction "NC_12") (pintype "passive+no_connect"))
    )
    (net (code "52") (name "unconnected-(U1D-NC-Pad13)") (class "Default")
      (node (ref "U1") (pin "13") (pinfunction "NC_13") (pintype "passive+no_connect"))
    )
    (net (code "53") (name "unconnected-(U1D-NC-Pad14)") (class "Default")
      (node (ref "U1") (pin "14") (pinfunction "NC_14") (pintype "passive+no_connect"))
    )
  )
)
